# LPCB220_-_DAC_A.net
KiCad netlist of a schematic drawn in Altium Designer
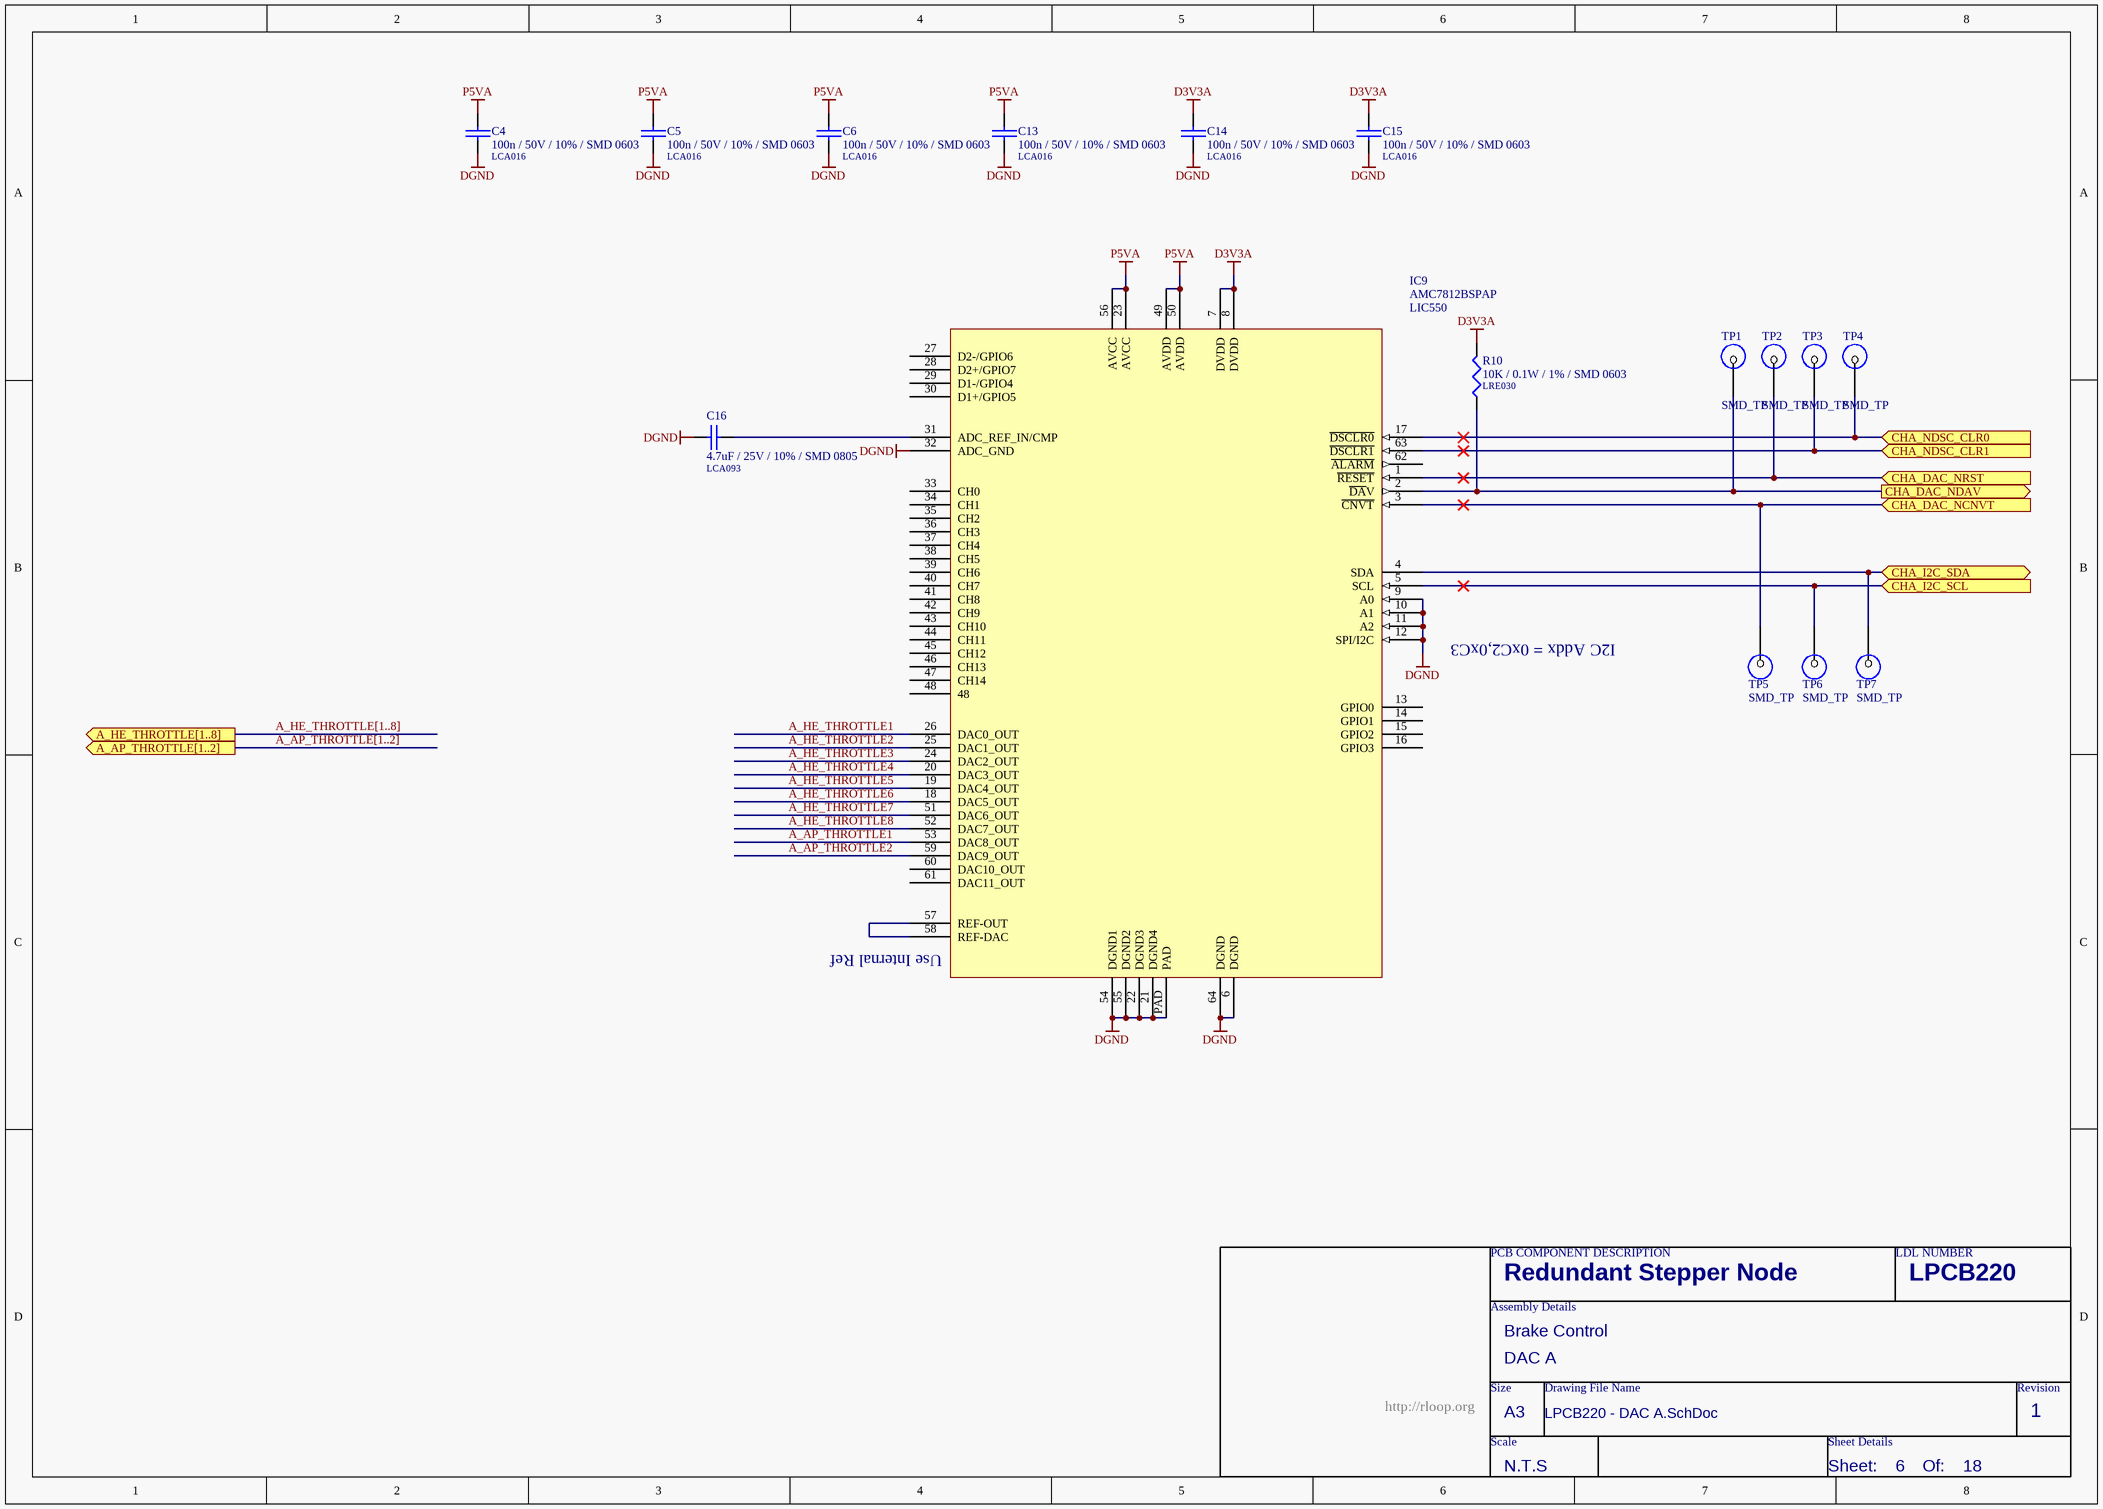
[diagram p0: LPCB220 - DAC A.SchDoc]

(export (version "E")
  (design (tool "Eeschema 10.0.6"))
  (components
    (comp (ref "C4")
      (value "100n / 50V / 10% / SMD 0603")
      (footprint "LFP011__CC1608-0603-IPC7351_B")
      (description "Capacitor, Ceramic Chip, 100nF (0.1uF), 50V, 5%, SMD 0603 [LCA016]")
      (fields (field (name "LDL_NUMBER") "LCA016"))
      (libsource (lib "LDL_Capacitors") (part "100n / 50V / 10% / SMD 0603"))
    )
    (comp (ref "C5")
      (value "100n / 50V / 10% / SMD 0603")
      (footprint "LFP011__CC1608-0603-IPC7351_B")
      (description "Capacitor, Ceramic Chip, 100nF (0.1uF), 50V, 5%, SMD 0603 [LCA016]")
      (fields (field (name "LDL_NUMBER") "LCA016"))
      (libsource (lib "LDL_Capacitors") (part "100n / 50V / 10% / SMD 0603"))
    )
    (comp (ref "C6")
      (value "100n / 50V / 10% / SMD 0603")
      (footprint "LFP011__CC1608-0603-IPC7351_B")
      (description "Capacitor, Ceramic Chip, 100nF (0.1uF), 50V, 5%, SMD 0603 [LCA016]")
      (fields (field (name "LDL_NUMBER") "LCA016"))
      (libsource (lib "LDL_Capacitors") (part "100n / 50V / 10% / SMD 0603"))
    )
    (comp (ref "C13")
      (value "100n / 50V / 10% / SMD 0603")
      (footprint "LFP011__CC1608-0603-IPC7351_B")
      (description "Capacitor, Ceramic Chip, 100nF (0.1uF), 50V, 5%, SMD 0603 [LCA016]")
      (fields (field (name "LDL_NUMBER") "LCA016"))
      (libsource (lib "LDL_Capacitors") (part "100n / 50V / 10% / SMD 0603"))
    )
    (comp (ref "C14")
      (value "100n / 50V / 10% / SMD 0603")
      (footprint "LFP011__CC1608-0603-IPC7351_B")
      (description "Capacitor, Ceramic Chip, 100nF (0.1uF), 50V, 5%, SMD 0603 [LCA016]")
      (fields (field (name "LDL_NUMBER") "LCA016"))
      (libsource (lib "LDL_Capacitors") (part "100n / 50V / 10% / SMD 0603"))
    )
    (comp (ref "C15")
      (value "100n / 50V / 10% / SMD 0603")
      (footprint "LFP011__CC1608-0603-IPC7351_B")
      (description "Capacitor, Ceramic Chip, 100nF (0.1uF), 50V, 5%, SMD 0603 [LCA016]")
      (fields (field (name "LDL_NUMBER") "LCA016"))
      (libsource (lib "LDL_Capacitors") (part "100n / 50V / 10% / SMD 0603"))
    )
    (comp (ref "C16")
      (value "4.7uF / 25V / 10% / SMD 0805")
      (footprint "LFP010__CC2012-0805-IPC7351_B")
      (description "Capacitor, Ceramic Chip, 4.7uF, 25V, 10%, SMD 0805 [LCA093]")
      (fields (field (name "LDL_NUMBER") "LCA093"))
      (libsource (lib "LDL_Capacitors") (part "4.7uF / 25V / 10% / SMD 0805"))
    )
    (comp (ref "IC9")
      (value "AMC7812BSPAP")
      (footprint "LFP134__H-QFP10X10-64N")
      (description "IC, ADC / DAC, SMD [LIC550]")
      (fields (field (name "LDL_NUMBER") "LIC550"))
      (libsource (lib "LDL_Semiconductors") (part "AMC7812BSPAP"))
    )
    (comp (ref "R10")
      (value "10K / 0.1W / 1% / SMD 0603")
      (footprint "LFP020__CR1608-0603-IPC7351_B")
      (description "Resistor, Ceramic Chip, 10K, 0.1W, 1%, SMD 0603 [LRE030]")
      (fields (field (name "LDL_NUMBER") "LRE030"))
      (libsource (lib "LDL_Resistors") (part "10K / 0.1W / 1% / SMD 0603"))
    )
    (comp (ref "TP1")
      (value "SMD_TP")
      (footprint "SMD-TP")
      (description "SMD Test Point")
      (libsource (lib "LDL_Connectors") (part "SMD_TP"))
    )
    (comp (ref "TP2")
      (value "SMD_TP")
      (footprint "SMD-TP")
      (description "SMD Test Point")
      (libsource (lib "LDL_Connectors") (part "SMD_TP"))
    )
    (comp (ref "TP3")
      (value "SMD_TP")
      (footprint "SMD-TP")
      (description "SMD Test Point")
      (libsource (lib "LDL_Connectors") (part "SMD_TP"))
    )
    (comp (ref "TP4")
      (value "SMD_TP")
      (footprint "SMD-TP")
      (description "SMD Test Point")
      (libsource (lib "LDL_Connectors") (part "SMD_TP"))
    )
    (comp (ref "TP5")
      (value "SMD_TP")
      (footprint "SMD-TP")
      (description "SMD Test Point")
      (libsource (lib "LDL_Connectors") (part "SMD_TP"))
    )
    (comp (ref "TP6")
      (value "SMD_TP")
      (footprint "SMD-TP")
      (description "SMD Test Point")
      (libsource (lib "LDL_Connectors") (part "SMD_TP"))
    )
    (comp (ref "TP7")
      (value "SMD_TP")
      (footprint "SMD-TP")
      (description "SMD Test Point")
      (libsource (lib "LDL_Connectors") (part "SMD_TP"))
    )
  )
  (nets
    (net (code "1") (name "/A_AP_THROTTLE1") (class "Default")
      (node (ref "IC9") (pin "53") (pinfunction "DAC8_OUT_53") (pintype "passive"))
    )
    (net (code "2") (name "/A_AP_THROTTLE2") (class "Default")
      (node (ref "IC9") (pin "59") (pinfunction "DAC9_OUT_59") (pintype "passive"))
    )
    (net (code "4") (name "/A_HE_THROTTLE1") (class "Default")
      (node (ref "IC9") (pin "26") (pinfunction "DAC0_OUT_26") (pintype "passive"))
    )
    (net (code "5") (name "/A_HE_THROTTLE2") (class "Default")
      (node (ref "IC9") (pin "25") (pinfunction "DAC1_OUT_25") (pintype "passive"))
    )
    (net (code "6") (name "/A_HE_THROTTLE3") (class "Default")
      (node (ref "IC9") (pin "24") (pinfunction "DAC2_OUT_24") (pintype "passive"))
    )
    (net (code "7") (name "/A_HE_THROTTLE4") (class "Default")
      (node (ref "IC9") (pin "20") (pinfunction "DAC3_OUT_20") (pintype "passive"))
    )
    (net (code "8") (name "/A_HE_THROTTLE5") (class "Default")
      (node (ref "IC9") (pin "19") (pinfunction "DAC4_OUT_19") (pintype "passive"))
    )
    (net (code "9") (name "/A_HE_THROTTLE6") (class "Default")
      (node (ref "IC9") (pin "18") (pinfunction "DAC5_OUT_18") (pintype "passive"))
    )
    (net (code "10") (name "/A_HE_THROTTLE7") (class "Default")
      (node (ref "IC9") (pin "51") (pinfunction "DAC6_OUT_51") (pintype "passive"))
    )
    (net (code "11") (name "/A_HE_THROTTLE8") (class "Default")
      (node (ref "IC9") (pin "52") (pinfunction "DAC7_OUT_52") (pintype "passive"))
    )
    (net (code "13") (name "/CHA_DAC_NCNVT") (class "Default")
      (node (ref "IC9") (pin "3") (pinfunction "~{CNVT}_3") (pintype "input"))
      (node (ref "TP5") (pin "1") (pintype "passive"))
    )
    (net (code "14") (name "/CHA_DAC_NDAV") (class "Default")
      (node (ref "IC9") (pin "2") (pinfunction "~{DA}V_2") (pintype "output"))
      (node (ref "R10") (pin "1") (pintype "passive"))
      (node (ref "TP1") (pin "1") (pintype "passive"))
    )
    (net (code "15") (name "/CHA_DAC_NRST") (class "Default")
      (node (ref "IC9") (pin "1") (pinfunction "~{RESET}_1") (pintype "input"))
      (node (ref "TP2") (pin "1") (pintype "passive"))
    )
    (net (code "16") (name "/CHA_I2C_SCL") (class "Default")
      (node (ref "IC9") (pin "5") (pinfunction "SCL_5") (pintype "input"))
      (node (ref "TP6") (pin "1") (pintype "passive"))
    )
    (net (code "17") (name "/CHA_I2C_SDA") (class "Default")
      (node (ref "IC9") (pin "4") (pinfunction "SDA_4") (pintype "passive"))
      (node (ref "TP7") (pin "1") (pintype "passive"))
    )
    (net (code "18") (name "/CHA_NDSC_CLR0") (class "Default")
      (node (ref "IC9") (pin "17") (pinfunction "~{DSCLR0}_17") (pintype "input"))
      (node (ref "TP4") (pin "1") (pintype "passive"))
    )
    (net (code "19") (name "/CHA_NDSC_CLR1") (class "Default")
      (node (ref "IC9") (pin "63") (pinfunction "~{DSCLR1}_63") (pintype "input"))
      (node (ref "TP3") (pin "1") (pintype "passive"))
    )
    (net (code "20") (name "D3V3A") (class "Default")
      (node (ref "C14") (pin "1") (pintype "passive"))
      (node (ref "C15") (pin "1") (pintype "passive"))
      (node (ref "IC9") (pin "7") (pinfunction "DVDD_7") (pintype "power_in"))
      (node (ref "IC9") (pin "8") (pinfunction "DVDD_8") (pintype "power_in"))
      (node (ref "R10") (pin "2") (pintype "passive"))
    )
    (net (code "21") (name "DGND") (class "Default")
      (node (ref "C13") (pin "2") (pintype "passive"))
      (node (ref "C14") (pin "2") (pintype "passive"))
      (node (ref "C15") (pin "2") (pintype "passive"))
      (node (ref "C16") (pin "1") (pintype "passive"))
      (node (ref "C4") (pin "2") (pintype "passive"))
      (node (ref "C5") (pin "2") (pintype "passive"))
      (node (ref "C6") (pin "2") (pintype "passive"))
      (node (ref "IC9") (pin "10") (pinfunction "A1_10") (pintype "input"))
      (node (ref "IC9") (pin "11") (pinfunction "A2_11") (pintype "input"))
      (node (ref "IC9") (pin "12") (pinfunction "SPI/I2C_12") (pintype "input"))
      (node (ref "IC9") (pin "21") (pinfunction "DGND4_21") (pintype "power_in"))
      (node (ref "IC9") (pin "22") (pinfunction "DGND3_22") (pintype "power_in"))
      (node (ref "IC9") (pin "32") (pinfunction "ADC_GND_32") (pintype "power_in"))
      (node (ref "IC9") (pin "54") (pinfunction "DGND1_54") (pintype "power_in"))
      (node (ref "IC9") (pin "55") (pinfunction "DGND2_55") (pintype "power_in"))
      (node (ref "IC9") (pin "6") (pinfunction "DGND_6") (pintype "power_in"))
      (node (ref "IC9") (pin "64") (pinfunction "DGND_64") (pintype "power_in"))
      (node (ref "IC9") (pin "9") (pinfunction "A0_9") (pintype "input"))
      (node (ref "IC9") (pin "PAD") (pinfunction "PAD_PAD") (pintype "power_in"))
    )
    (net (code "22") (name "Net-(IC9-ADC_REF_IN{slash}CMP)") (class "Default")
      (node (ref "C16") (pin "2") (pintype "passive"))
      (node (ref "IC9") (pin "31") (pinfunction "ADC_REF_IN/CMP_31") (pintype "passive"))
    )
    (net (code "23") (name "Net-(IC9-REF-DAC)") (class "Default")
      (node (ref "IC9") (pin "57") (pinfunction "REF-OUT_57") (pintype "passive"))
      (node (ref "IC9") (pin "58") (pinfunction "REF-DAC_58") (pintype "passive"))
    )
    (net (code "24") (name "P5VA") (class "Default")
      (node (ref "C13") (pin "1") (pintype "passive"))
      (node (ref "C4") (pin "1") (pintype "passive"))
      (node (ref "C5") (pin "1") (pintype "passive"))
      (node (ref "C6") (pin "1") (pintype "passive"))
      (node (ref "IC9") (pin "23") (pinfunction "AVCC_23") (pintype "power_in"))
      (node (ref "IC9") (pin "49") (pinfunction "AVDD_49") (pintype "power_in"))
      (node (ref "IC9") (pin "50") (pinfunction "AVDD_50") (pintype "power_in"))
      (node (ref "IC9") (pin "56") (pinfunction "AVCC_56") (pintype "power_in"))
    )
    (net (code "25") (name "unconnected-(IC9-CH0-Pad33)") (class "Default")
      (node (ref "IC9") (pin "33") (pinfunction "CH0_33") (pintype "passive"))
    )
    (net (code "26") (name "unconnected-(IC9-CH1-Pad34)") (class "Default")
      (node (ref "IC9") (pin "34") (pinfunction "CH1_34") (pintype "passive"))
    )
    (net (code "27") (name "unconnected-(IC9-CH2-Pad35)") (class "Default")
      (node (ref "IC9") (pin "35") (pinfunction "CH2_35") (pintype "passive"))
    )
    (net (code "28") (name "unconnected-(IC9-CH3-Pad36)") (class "Default")
      (node (ref "IC9") (pin "36") (pinfunction "CH3_36") (pintype "passive"))
    )
    (net (code "29") (name "unconnected-(IC9-CH4-Pad37)") (class "Default")
      (node (ref "IC9") (pin "37") (pinfunction "CH4_37") (pintype "passive"))
    )
    (net (code "30") (name "unconnected-(IC9-CH5-Pad38)") (class "Default")
      (node (ref "IC9") (pin "38") (pinfunction "CH5_38") (pintype "passive"))
    )
    (net (code "31") (name "unconnected-(IC9-CH6-Pad39)") (class "Default")
      (node (ref "IC9") (pin "39") (pinfunction "CH6_39") (pintype "passive"))
    )
    (net (code "32") (name "unconnected-(IC9-CH7-Pad40)") (class "Default")
      (node (ref "IC9") (pin "40") (pinfunction "CH7_40") (pintype "passive"))
    )
    (net (code "33") (name "unconnected-(IC9-CH8-Pad41)") (class "Default")
      (node (ref "IC9") (pin "41") (pinfunction "CH8_41") (pintype "passive"))
    )
    (net (code "34") (name "unconnected-(IC9-CH9-Pad42)") (class "Default")
      (node (ref "IC9") (pin "42") (pinfunction "CH9_42") (pintype "passive"))
    )
    (net (code "35") (name "unconnected-(IC9-CH10-Pad43)") (class "Default")
      (node (ref "IC9") (pin "43") (pinfunction "CH10_43") (pintype "passive"))
    )
    (net (code "36") (name "unconnected-(IC9-CH11-Pad44)") (class "Default")
      (node (ref "IC9") (pin "44") (pinfunction "CH11_44") (pintype "passive"))
    )
    (net (code "37") (name "unconnected-(IC9-CH12-Pad45)") (class "Default")
      (node (ref "IC9") (pin "45") (pinfunction "CH12_45") (pintype "passive"))
    )
    (net (code "38") (name "unconnected-(IC9-CH13-Pad46)") (class "Default")
      (node (ref "IC9") (pin "46") (pinfunction "CH13_46") (pintype "passive"))
    )
    (net (code "39") (name "unconnected-(IC9-CH14-Pad47)") (class "Default")
      (node (ref "IC9") (pin "47") (pinfunction "CH14_47") (pintype "passive"))
    )
    (net (code "40") (name "unconnected-(IC9-D1+{slash}GPIO5-Pad30)") (class "Default")
      (node (ref "IC9") (pin "30") (pinfunction "D1+/GPIO5_30") (pintype "passive"))
    )
    (net (code "41") (name "unconnected-(IC9-D1-{slash}GPIO4-Pad29)") (class "Default")
      (node (ref "IC9") (pin "29") (pinfunction "D1-/GPIO4_29") (pintype "passive"))
    )
    (net (code "42") (name "unconnected-(IC9-D2+{slash}GPIO7-Pad28)") (class "Default")
      (node (ref "IC9") (pin "28") (pinfunction "D2+/GPIO7_28") (pintype "passive"))
    )
    (net (code "43") (name "unconnected-(IC9-D2-{slash}GPIO6-Pad27)") (class "Default")
      (node (ref "IC9") (pin "27") (pinfunction "D2-/GPIO6_27") (pintype "passive"))
    )
    (net (code "44") (name "unconnected-(IC9-DAC10_OUT-Pad60)") (class "Default")
      (node (ref "IC9") (pin "60") (pinfunction "DAC10_OUT_60") (pintype "passive"))
    )
    (net (code "45") (name "unconnected-(IC9-DAC11_OUT-Pad61)") (class "Default")
      (node (ref "IC9") (pin "61") (pinfunction "DAC11_OUT_61") (pintype "passive"))
    )
    (net (code "46") (name "unconnected-(IC9-GPIO0-Pad13)") (class "Default")
      (node (ref "IC9") (pin "13") (pinfunction "GPIO0_13") (pintype "passive"))
    )
    (net (code "47") (name "unconnected-(IC9-GPIO1-Pad14)") (class "Default")
      (node (ref "IC9") (pin "14") (pinfunction "GPIO1_14") (pintype "passive"))
    )
    (net (code "48") (name "unconnected-(IC9-GPIO2-Pad15)") (class "Default")
      (node (ref "IC9") (pin "15") (pinfunction "GPIO2_15") (pintype "passive"))
    )
    (net (code "49") (name "unconnected-(IC9-GPIO3-Pad16)") (class "Default")
      (node (ref "IC9") (pin "16") (pinfunction "GPIO3_16") (pintype "passive"))
    )
    (net (code "50") (name "unconnected-(IC9-Pad48)") (class "Default")
      (node (ref "IC9") (pin "48") (pinfunction "48_48") (pintype "passive"))
    )
    (net (code "51") (name "unconnected-(IC9-~{ALARM}-Pad62)") (class "Default")
      (node (ref "IC9") (pin "62") (pinfunction "~{ALARM}_62") (pintype "output"))
    )
  )
)
